# Electronic_Design_after_review_sch.net
KiCad netlist of a schematic drawn in EAGLE
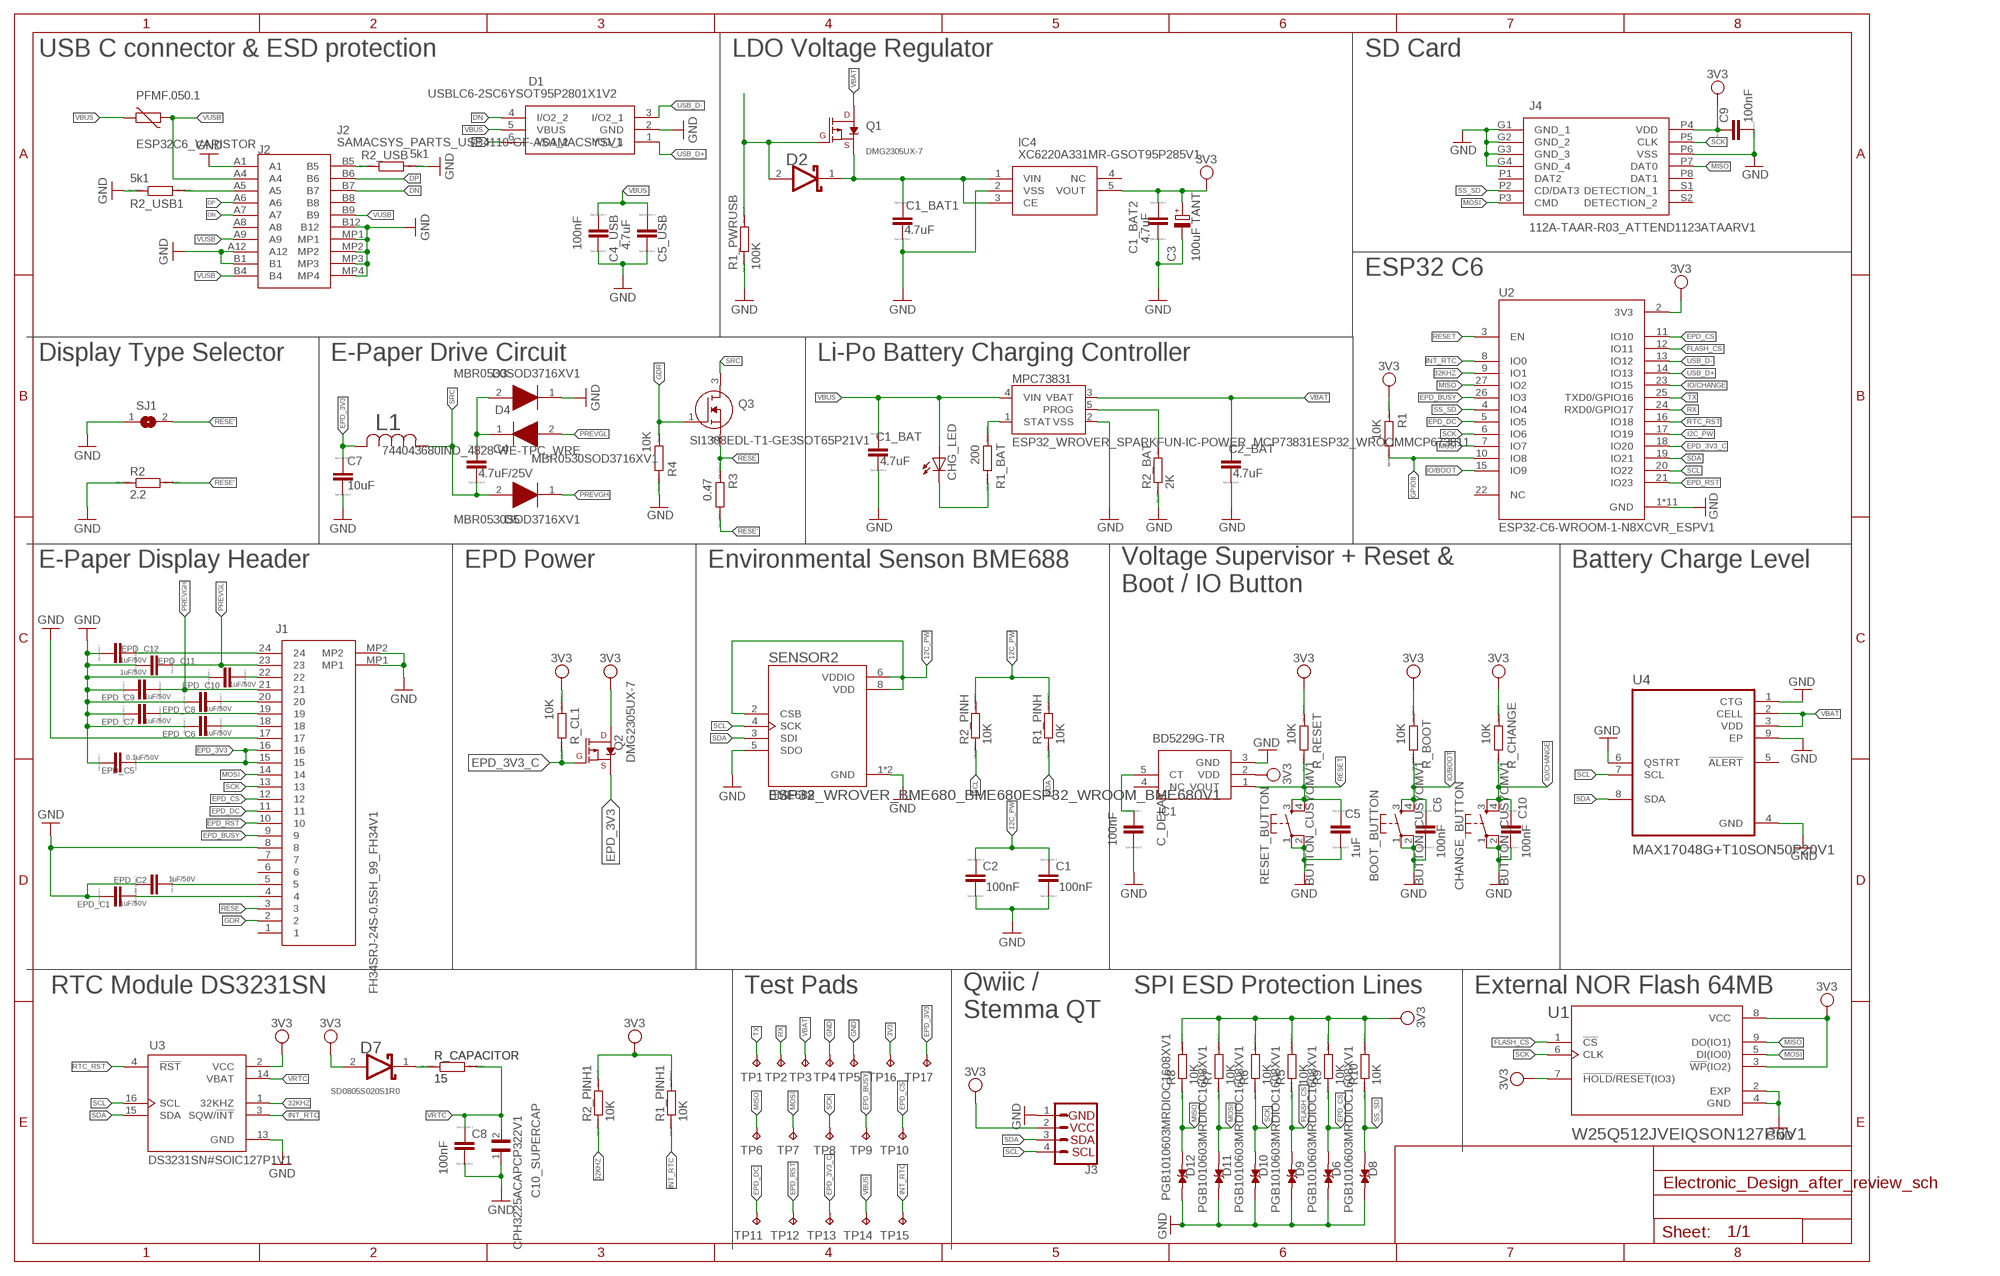
[diagram p0: schematic, sheet 1]

(export (version "E")
  (design (tool "Eeschema 10.0.6"))
  (components
    (comp (ref "BOOT_BUTTON")
      (value "BUTTON_CUSYOMV1")
      (footprint "eagle-import:MYBUTTON")
      (libsource (lib "eagle-import") (part "BUTTON_CUSYOMV1"))
    )
    (comp (ref "C1")
      (value "100nF")
      (footprint "eagle-import:EAGLE-LTSPICE_C0402")
      (libsource (lib "eagle-import") (part "EAGLE-LTSPICE_C"))
    )
    (comp (ref "C1_BAT")
      (value "4.7uF")
      (footprint "eagle-import:ESP32_WROVER_EAGLE-LTSPICE_C0402")
      (libsource (lib "eagle-import") (part "ESP32_WROVER_EAGLE-LTSPICE_C"))
    )
    (comp (ref "C1_BAT1")
      (value "4.7uF")
      (footprint "eagle-import:ESP32_WROVER_EAGLE-LTSPICE_C0402")
      (libsource (lib "eagle-import") (part "ESP32_WROVER_EAGLE-LTSPICE_C"))
    )
    (comp (ref "C1_BAT2")
      (value "4.7uF")
      (footprint "eagle-import:ESP32_WROVER_EAGLE-LTSPICE_C0402")
      (libsource (lib "eagle-import") (part "ESP32_WROVER_EAGLE-LTSPICE_C"))
    )
    (comp (ref "C2")
      (value "100nF")
      (footprint "eagle-import:EAGLE-LTSPICE_C0402")
      (libsource (lib "eagle-import") (part "EAGLE-LTSPICE_C"))
    )
    (comp (ref "C2_BAT")
      (value "4.7uF")
      (footprint "eagle-import:ESP32_WROVER_EAGLE-LTSPICE_C0402")
      (libsource (lib "eagle-import") (part "ESP32_WROVER_EAGLE-LTSPICE_C"))
    )
    (comp (ref "C3")
      (value "100uF TANT")
      (footprint "eagle-import:RCL_CT3528")
      (libsource (lib "eagle-import") (part "RCL_CPOL-EU"))
    )
    (comp (ref "C4")
      (value "4.7uF/25V")
      (footprint "eagle-import:ESP32_WROVER_EAGLE-LTSPICE_C0402")
      (libsource (lib "eagle-import") (part "ESP32_WROVER_EAGLE-LTSPICE_C"))
    )
    (comp (ref "C4_USB")
      (value "100nF")
      (footprint "eagle-import:ESP32_WROVER_EAGLE-LTSPICE_C0402")
      (libsource (lib "eagle-import") (part "ESP32_WROVER_EAGLE-LTSPICE_C"))
    )
    (comp (ref "C5")
      (value "1uF")
      (footprint "eagle-import:EAGLE-LTSPICE_C0402")
      (libsource (lib "eagle-import") (part "EAGLE-LTSPICE_C"))
    )
    (comp (ref "C5_USB")
      (value "4.7uF")
      (footprint "eagle-import:ESP32_WROVER_EAGLE-LTSPICE_C0402")
      (libsource (lib "eagle-import") (part "ESP32_WROVER_EAGLE-LTSPICE_C"))
    )
    (comp (ref "C6")
      (value "100nF")
      (footprint "eagle-import:EAGLE-LTSPICE_C0402")
      (libsource (lib "eagle-import") (part "EAGLE-LTSPICE_C"))
    )
    (comp (ref "C7")
      (value "10uF")
      (footprint "eagle-import:ESP32_WROVER_EAGLE-LTSPICE_C0402")
      (libsource (lib "eagle-import") (part "ESP32_WROVER_EAGLE-LTSPICE_C"))
    )
    (comp (ref "C8")
      (value "100nF")
      (footprint "eagle-import:EAGLE-LTSPICE_C0402")
      (libsource (lib "eagle-import") (part "EAGLE-LTSPICE_C"))
    )
    (comp (ref "C9")
      (value "100nF")
      (footprint "eagle-import:ESP32_WROVER_EAGLE-LTSPICE_C0402")
      (libsource (lib "eagle-import") (part "ESP32_WROVER_EAGLE-LTSPICE_C"))
    )
    (comp (ref "C10")
      (value "100nF")
      (footprint "eagle-import:EAGLE-LTSPICE_C0402")
      (libsource (lib "eagle-import") (part "EAGLE-LTSPICE_C"))
    )
    (comp (ref "C10_SUPERCAP")
      (value "CPH3225ACAPCP322V1")
      (footprint "eagle-import:CAPCP3225X100N")
      (libsource (lib "eagle-import") (part "CPH3225ACAPCP322V1"))
    )
    (comp (ref "CHANGE_BUTTON")
      (value "BUTTON_CUSYOMV1")
      (footprint "eagle-import:MYBUTTON")
      (libsource (lib "eagle-import") (part "BUTTON_CUSYOMV1"))
    )
    (comp (ref "CHG_LED")
      (value "ADAFRUIT_LED")
      (footprint "eagle-import:ADAFRUIT_CHIP-LED0603")
      (libsource (lib "eagle-import") (part "ADAFRUIT_LED"))
    )
    (comp (ref "C_DELAY")
      (value "100nF")
      (footprint "eagle-import:EAGLE-LTSPICE_C0402")
      (libsource (lib "eagle-import") (part "EAGLE-LTSPICE_C"))
    )
    (comp (ref "D1")
      (value "USBLC6-2SC6YSOT95P2801X1V2")
      (footprint "eagle-import:SOT95P280X145-6N")
      (libsource (lib "eagle-import") (part "USBLC6-2SC6YSOT95P2801X1V2"))
    )
    (comp (ref "D2")
      (value "ESP32_WROVER_AVX---SD0805S020S1R0_AVX_SD0805S020S1R0_0_0")
      (footprint "eagle-import:ESP32_WROVER_AVX---SD0805S020S1R0_AVX_SD0805S020S1R0_0")
      (libsource (lib "eagle-import") (part "ESP32_WROVER_AVX---SD0805S020S1R0_AVX_SD0805S020S1R0_0_0"))
    )
    (comp (ref "D3")
      (value "MBR0530SOD3716XV1")
      (footprint "eagle-import:SOD3716X135N")
      (libsource (lib "eagle-import") (part "MBR0530SOD3716XV1"))
    )
    (comp (ref "D4")
      (value "MBR0530SOD3716XV1")
      (footprint "eagle-import:SOD3716X135N")
      (libsource (lib "eagle-import") (part "MBR0530SOD3716XV1"))
    )
    (comp (ref "D5")
      (value "MBR0530SOD3716XV1")
      (footprint "eagle-import:SOD3716X135N")
      (libsource (lib "eagle-import") (part "MBR0530SOD3716XV1"))
    )
    (comp (ref "D6")
      (value "PGB1010603MRDIOC1608XV1")
      (footprint "eagle-import:DIOC1608X36N")
      (libsource (lib "eagle-import") (part "PGB1010603MRDIOC1608XV1"))
    )
    (comp (ref "D7")
      (value "ESP32_WROVER_AVX---SD0805S020S1R0_AVX_SD0805S020S1R0_0_0")
      (footprint "eagle-import:ESP32_WROVER_AVX---SD0805S020S1R0_AVX_SD0805S020S1R0_0")
      (libsource (lib "eagle-import") (part "ESP32_WROVER_AVX---SD0805S020S1R0_AVX_SD0805S020S1R0_0_0"))
    )
    (comp (ref "D8")
      (value "PGB1010603MRDIOC1608XV1")
      (footprint "eagle-import:DIOC1608X36N")
      (libsource (lib "eagle-import") (part "PGB1010603MRDIOC1608XV1"))
    )
    (comp (ref "D9")
      (value "PGB1010603MRDIOC1608XV1")
      (footprint "eagle-import:DIOC1608X36N")
      (libsource (lib "eagle-import") (part "PGB1010603MRDIOC1608XV1"))
    )
    (comp (ref "D10")
      (value "PGB1010603MRDIOC1608XV1")
      (footprint "eagle-import:DIOC1608X36N")
      (libsource (lib "eagle-import") (part "PGB1010603MRDIOC1608XV1"))
    )
    (comp (ref "D11")
      (value "PGB1010603MRDIOC1608XV1")
      (footprint "eagle-import:DIOC1608X36N")
      (libsource (lib "eagle-import") (part "PGB1010603MRDIOC1608XV1"))
    )
    (comp (ref "D12")
      (value "PGB1010603MRDIOC1608XV1")
      (footprint "eagle-import:DIOC1608X36N")
      (libsource (lib "eagle-import") (part "PGB1010603MRDIOC1608XV1"))
    )
    (comp (ref "EPD_C1")
      (value "1uF/50V")
      (footprint "eagle-import:EAGLE-LTSPICE_C0402")
      (libsource (lib "eagle-import") (part "EAGLE-LTSPICE_C"))
    )
    (comp (ref "EPD_C2")
      (value "1uF/50V")
      (footprint "eagle-import:EAGLE-LTSPICE_C0402")
      (libsource (lib "eagle-import") (part "EAGLE-LTSPICE_C"))
    )
    (comp (ref "EPD_C5")
      (value "0.1uF/50V")
      (footprint "eagle-import:EAGLE-LTSPICE_C0402")
      (libsource (lib "eagle-import") (part "EAGLE-LTSPICE_C"))
    )
    (comp (ref "EPD_C6")
      (value "1uF/50V")
      (footprint "eagle-import:EAGLE-LTSPICE_C0402")
      (libsource (lib "eagle-import") (part "EAGLE-LTSPICE_C"))
    )
    (comp (ref "EPD_C7")
      (value "1uF/50V")
      (footprint "eagle-import:EAGLE-LTSPICE_C0402")
      (libsource (lib "eagle-import") (part "EAGLE-LTSPICE_C"))
    )
    (comp (ref "EPD_C8")
      (value "1uF/50V")
      (footprint "eagle-import:EAGLE-LTSPICE_C0402")
      (libsource (lib "eagle-import") (part "EAGLE-LTSPICE_C"))
    )
    (comp (ref "EPD_C9")
      (value "1uF/50V")
      (footprint "eagle-import:EAGLE-LTSPICE_C0402")
      (libsource (lib "eagle-import") (part "EAGLE-LTSPICE_C"))
    )
    (comp (ref "EPD_C10")
      (value "1uF/50V")
      (footprint "eagle-import:EAGLE-LTSPICE_C0402")
      (libsource (lib "eagle-import") (part "EAGLE-LTSPICE_C"))
    )
    (comp (ref "EPD_C11")
      (value "1uF/50V")
      (footprint "eagle-import:EAGLE-LTSPICE_C0402")
      (libsource (lib "eagle-import") (part "EAGLE-LTSPICE_C"))
    )
    (comp (ref "EPD_C12")
      (value "1uF/50V")
      (footprint "eagle-import:EAGLE-LTSPICE_C0402")
      (libsource (lib "eagle-import") (part "EAGLE-LTSPICE_C"))
    )
    (comp (ref "IC1")
      (value "BD5229G-TR")
      (footprint "eagle-import:SOT95P280X120-5N")
      (libsource (lib "eagle-import") (part "BD5229G-TR"))
    )
    (comp (ref "IC4")
      (value "XC6220A331MR-GSOT95P285V1")
      (footprint "eagle-import:SOT95P280X120-5N")
      (libsource (lib "eagle-import") (part "XC6220A331MR-GSOT95P285V1"))
    )
    (comp (ref "J1")
      (value "FH34SRJ-24S-0.5SH_99_FH34V1")
      (footprint "eagle-import:FH34SRJ24S05SH99")
      (libsource (lib "eagle-import") (part "FH34SRJ-24S-0.5SH_99_FH34V1"))
    )
    (comp (ref "J2")
      (value "SAMACSYS_PARTS_USB4110-GF-ASAMACSYSV1")
      (footprint "eagle-import:SAMACSYS_PARTS_USB4110GFA")
      (libsource (lib "eagle-import") (part "SAMACSYS_PARTS_USB4110-GF-ASAMACSYSV1"))
    )
    (comp (ref "J3")
      (value "QWIIC_RIGHT_ANGLE")
      (footprint "eagle-import:JST04_1MM_RA")
      (libsource (lib "eagle-import") (part "QWIIC_CONNECTOR"))
    )
    (comp (ref "J4")
      (value "112A-TAAR-R03_ATTEND1123ATAARV1")
      (footprint "eagle-import:112ATAARR03ATTEND")
      (libsource (lib "eagle-import") (part "112A-TAAR-R03_ATTEND1123ATAARV1"))
    )
    (comp (ref "L1")
      (value "744043680IND_4828-WE-TPC_WRE")
      (footprint "eagle-import:IND_4828-WE-TPC_WRE")
      (libsource (lib "eagle-import") (part "744043680"))
    )
    (comp (ref "MPC73831")
      (value "ESP32_WROVER_SPARKFUN-IC-POWER_MCP73831ESP32_WROOMMCP673811")
      (footprint "eagle-import:ESP32_WROVER_SPARKFUN-IC-POWER_SOT23-5")
      (libsource (lib "eagle-import") (part "ESP32_WROVER_SPARKFUN-IC-POWER_MCP73831ESP32_WROOMMCP673811"))
    )
    (comp (ref "PFMF.050.1")
      (value "ESP32C6_VARISTOR")
      (footprint "eagle-import:ESP32C6_VARISTOR_CT_CN1812")
      (libsource (lib "eagle-import") (part "ESP32C6_VARISTOR"))
    )
    (comp (ref "Q1")
      (value "20V/4.2A/52mΩ/1.4W")
      (footprint "eagle-import:ESP32_WROVER_SPARKFUN-DISCRETESEMI_SOT23-3")
      (libsource (lib "eagle-import") (part "ESP32_WROVER_SPARKFUN-DISCRETESEMI_MOSFET_PCH"))
    )
    (comp (ref "Q2")
      (value "20V/4.2A/52mΩ/1.4W")
      (footprint "eagle-import:ESP32_WROVER_SPARKFUN-DISCRETESEMI_SOT23-3")
      (libsource (lib "eagle-import") (part "ESP32_WROVER_SPARKFUN-DISCRETESEMI_MOSFET_PCH"))
    )
    (comp (ref "Q3")
      (value "SI1308EDL-T1-GE3SOT65P21V1")
      (footprint "eagle-import:SOT65P210X110-3N")
      (libsource (lib "eagle-import") (part "SI1308EDL-T1-GE3SOT65P21V1"))
    )
    (comp (ref "R1")
      (value "10K")
      (footprint "eagle-import:ESP32_WROVER_EAGLE-LTSPICE_R0402")
      (libsource (lib "eagle-import") (part "ESP32_WROVER_EAGLE-LTSPICE_R"))
    )
    (comp (ref "R1_BAT")
      (value "200")
      (footprint "eagle-import:ESP32_WROVER_EAGLE-LTSPICE_R0402")
      (libsource (lib "eagle-import") (part "ESP32_WROVER_EAGLE-LTSPICE_R"))
    )
    (comp (ref "R1_PINH")
      (value "10K")
      (footprint "eagle-import:ESP32_WROVER_EAGLE-LTSPICE_R0402")
      (libsource (lib "eagle-import") (part "ESP32_WROVER_EAGLE-LTSPICE_R"))
    )
    (comp (ref "R1_PINH1")
      (value "10K")
      (footprint "eagle-import:ESP32_WROVER_EAGLE-LTSPICE_R0402")
      (libsource (lib "eagle-import") (part "ESP32_WROVER_EAGLE-LTSPICE_R"))
    )
    (comp (ref "R1_PWRUSB")
      (value "100K")
      (footprint "eagle-import:ESP32_WROVER_EAGLE-LTSPICE_R0402")
      (libsource (lib "eagle-import") (part "ESP32_WROVER_EAGLE-LTSPICE_R"))
    )
    (comp (ref "R2")
      (value "2.2")
      (footprint "eagle-import:ESP32_WROVER_EAGLE-LTSPICE_R0402")
      (libsource (lib "eagle-import") (part "ESP32_WROVER_EAGLE-LTSPICE_R"))
    )
    (comp (ref "R2_BAT")
      (value "2K")
      (footprint "eagle-import:ESP32_WROVER_EAGLE-LTSPICE_R0402")
      (libsource (lib "eagle-import") (part "ESP32_WROVER_EAGLE-LTSPICE_R"))
    )
    (comp (ref "R2_PINH")
      (value "10K")
      (footprint "eagle-import:ESP32_WROVER_EAGLE-LTSPICE_R0402")
      (libsource (lib "eagle-import") (part "ESP32_WROVER_EAGLE-LTSPICE_R"))
    )
    (comp (ref "R2_PINH1")
      (value "10K")
      (footprint "eagle-import:ESP32_WROVER_EAGLE-LTSPICE_R0402")
      (libsource (lib "eagle-import") (part "ESP32_WROVER_EAGLE-LTSPICE_R"))
    )
    (comp (ref "R2_USB")
      (value "5k1")
      (footprint "eagle-import:ESP32_WROVER_EAGLE-LTSPICE_R0402")
      (libsource (lib "eagle-import") (part "ESP32_WROVER_EAGLE-LTSPICE_R"))
    )
    (comp (ref "R2_USB1")
      (value "5k1")
      (footprint "eagle-import:ESP32_WROVER_EAGLE-LTSPICE_R0402")
      (libsource (lib "eagle-import") (part "ESP32_WROVER_EAGLE-LTSPICE_R"))
    )
    (comp (ref "R3")
      (value "0.47")
      (footprint "eagle-import:ESP32_WROVER_EAGLE-LTSPICE_R0402")
      (libsource (lib "eagle-import") (part "ESP32_WROVER_EAGLE-LTSPICE_R"))
    )
    (comp (ref "R4")
      (value "10K")
      (footprint "eagle-import:ESP32_WROVER_EAGLE-LTSPICE_R0402")
      (libsource (lib "eagle-import") (part "ESP32_WROVER_EAGLE-LTSPICE_R"))
    )
    (comp (ref "R5")
      (value "10K")
      (footprint "eagle-import:ESP32_WROVER_EAGLE-LTSPICE_R0402")
      (libsource (lib "eagle-import") (part "ESP32_WROVER_EAGLE-LTSPICE_R"))
    )
    (comp (ref "R6")
      (value "10K")
      (footprint "eagle-import:ESP32_WROVER_EAGLE-LTSPICE_R0402")
      (libsource (lib "eagle-import") (part "ESP32_WROVER_EAGLE-LTSPICE_R"))
    )
    (comp (ref "R7")
      (value "10K")
      (footprint "eagle-import:ESP32_WROVER_EAGLE-LTSPICE_R0402")
      (libsource (lib "eagle-import") (part "ESP32_WROVER_EAGLE-LTSPICE_R"))
    )
    (comp (ref "R8")
      (value "10K")
      (footprint "eagle-import:ESP32_WROVER_EAGLE-LTSPICE_R0402")
      (libsource (lib "eagle-import") (part "ESP32_WROVER_EAGLE-LTSPICE_R"))
    )
    (comp (ref "R9")
      (value "10K")
      (footprint "eagle-import:ESP32_WROVER_EAGLE-LTSPICE_R0402")
      (libsource (lib "eagle-import") (part "ESP32_WROVER_EAGLE-LTSPICE_R"))
    )
    (comp (ref "R10")
      (value "10K")
      (footprint "eagle-import:ESP32_WROVER_EAGLE-LTSPICE_R0402")
      (libsource (lib "eagle-import") (part "ESP32_WROVER_EAGLE-LTSPICE_R"))
    )
    (comp (ref "RESET_BUTTON")
      (value "BUTTON_CUSYOMV1")
      (footprint "eagle-import:MYBUTTON")
      (libsource (lib "eagle-import") (part "BUTTON_CUSYOMV1"))
    )
    (comp (ref "R_BOOT")
      (value "10K")
      (footprint "eagle-import:ESP32_WROVER_EAGLE-LTSPICE_R0402")
      (libsource (lib "eagle-import") (part "ESP32_WROVER_EAGLE-LTSPICE_R"))
    )
    (comp (ref "R_CAPACITOR")
      (value "15")
      (footprint "eagle-import:ESP32_WROVER_EAGLE-LTSPICE_R0402")
      (libsource (lib "eagle-import") (part "ESP32_WROVER_EAGLE-LTSPICE_R"))
    )
    (comp (ref "R_CHANGE")
      (value "10K")
      (footprint "eagle-import:ESP32_WROVER_EAGLE-LTSPICE_R0402")
      (libsource (lib "eagle-import") (part "ESP32_WROVER_EAGLE-LTSPICE_R"))
    )
    (comp (ref "R_CL1")
      (value "10K")
      (footprint "eagle-import:ESP32_WROVER_EAGLE-LTSPICE_R0402")
      (libsource (lib "eagle-import") (part "ESP32_WROVER_EAGLE-LTSPICE_R"))
    )
    (comp (ref "R_RESET")
      (value "10K")
      (footprint "eagle-import:ESP32_WROVER_EAGLE-LTSPICE_R0402")
      (libsource (lib "eagle-import") (part "ESP32_WROVER_EAGLE-LTSPICE_R"))
    )
    (comp (ref "SENSOR2")
      (value "ESP32_WROVER_BME680_BME680ESP32_WROOM_BME680V1")
      (footprint "eagle-import:ESP32_WROVER_BME680_PSON80P300X300X100-8N")
      (libsource (lib "eagle-import") (part "ESP32_WROVER_BME680_BME680ESP32_WROOM_BME680V1"))
    )
    (comp (ref "SJ1")
      (value "SJSJV1")
      (footprint "eagle-import:SJ")
      (libsource (lib "eagle-import") (part "SJSJV1"))
    )
    (comp (ref "TP1")
      (value "TP")
      (footprint "eagle-import:TP20R")
      (libsource (lib "eagle-import") (part "TP"))
    )
    (comp (ref "TP2")
      (value "TP")
      (footprint "eagle-import:TP20R")
      (libsource (lib "eagle-import") (part "TP"))
    )
    (comp (ref "TP3")
      (value "TP")
      (footprint "eagle-import:TP20R")
      (libsource (lib "eagle-import") (part "TP"))
    )
    (comp (ref "TP4")
      (value "TP")
      (footprint "eagle-import:TP20R")
      (libsource (lib "eagle-import") (part "TP"))
    )
    (comp (ref "TP5")
      (value "TP")
      (footprint "eagle-import:TP20R")
      (libsource (lib "eagle-import") (part "TP"))
    )
    (comp (ref "TP6")
      (value "TP")
      (footprint "eagle-import:TP20R")
      (libsource (lib "eagle-import") (part "TP"))
    )
    (comp (ref "TP7")
      (value "TP")
      (footprint "eagle-import:TP20R")
      (libsource (lib "eagle-import") (part "TP"))
    )
    (comp (ref "TP8")
      (value "TP")
      (footprint "eagle-import:TP20R")
      (libsource (lib "eagle-import") (part "TP"))
    )
    (comp (ref "TP9")
      (value "TP")
      (footprint "eagle-import:TP20R")
      (libsource (lib "eagle-import") (part "TP"))
    )
    (comp (ref "TP10")
      (value "TP")
      (footprint "eagle-import:TP20R")
      (libsource (lib "eagle-import") (part "TP"))
    )
    (comp (ref "TP11")
      (value "TP")
      (footprint "eagle-import:TP20R")
      (libsource (lib "eagle-import") (part "TP"))
    )
    (comp (ref "TP12")
      (value "TP")
      (footprint "eagle-import:TP20R")
      (libsource (lib "eagle-import") (part "TP"))
    )
    (comp (ref "TP13")
      (value "TP")
      (footprint "eagle-import:TP20R")
      (libsource (lib "eagle-import") (part "TP"))
    )
    (comp (ref "TP14")
      (value "TP")
      (footprint "eagle-import:TP20R")
      (libsource (lib "eagle-import") (part "TP"))
    )
    (comp (ref "TP15")
      (value "TP")
      (footprint "eagle-import:TP20R")
      (libsource (lib "eagle-import") (part "TP"))
    )
    (comp (ref "TP16")
      (value "TP")
      (footprint "eagle-import:TP20R")
      (libsource (lib "eagle-import") (part "TP"))
    )
    (comp (ref "TP17")
      (value "TP")
      (footprint "eagle-import:TP20R")
      (libsource (lib "eagle-import") (part "TP"))
    )
    (comp (ref "U1")
      (value "W25Q512JVEIQSON127P6V1")
      (footprint "eagle-import:SON127P600X800X80-9N")
      (libsource (lib "eagle-import") (part "W25Q512JVEIQSON127P6V1"))
    )
    (comp (ref "U2")
      (value "ESP32-C6-WROOM-1-N8XCVR_ESPV1")
      (footprint "eagle-import:XCVR_ESP32-C6-WROOM-1-N8")
      (libsource (lib "eagle-import") (part "ESP32-C6-WROOM-1-N8XCVR_ESPV1"))
    )
    (comp (ref "U3")
      (value "DS3231SN#SOIC127P1V1")
      (footprint "eagle-import:SOIC127P1032X265-16N")
      (libsource (lib "eagle-import") (part "DS3231SN#SOIC127P1V1"))
    )
    (comp (ref "U4")
      (value "MAX17048G+T10SON50P20V1")
      (footprint "eagle-import:SON50P200X200X80-9N")
      (libsource (lib "eagle-import") (part "MAX17048G+T10SON50P20V1"))
    )
  )
  (nets
    (net (code "1") (name "3V3") (class "Default")
      (node (ref "C1_BAT2") (pin "1") (pinfunction "1_1") (pintype "passive"))
      (node (ref "C3") (pin "+") (pinfunction "+_+") (pintype "passive"))
      (node (ref "C9") (pin "1") (pinfunction "1_1") (pintype "passive"))
      (node (ref "D7") (pin "2") (pinfunction "ANODE_2") (pintype "bidirectional"))
      (node (ref "IC1") (pin "2") (pinfunction "VDD_2") (pintype "bidirectional"))
      (node (ref "IC4") (pin "5") (pinfunction "VOUT_5") (pintype "bidirectional"))
      (node (ref "J3") (pin "2") (pinfunction "2_2") (pintype "power_in"))
      (node (ref "J4") (pin "P4") (pinfunction "VDD_P4") (pintype "bidirectional"))
      (node (ref "Q2") (pin "3") (pinfunction "D_3") (pintype "bidirectional"))
      (node (ref "R1") (pin "2") (pinfunction "2_2") (pintype "passive"))
      (node (ref "R10") (pin "2") (pinfunction "2_2") (pintype "passive"))
      (node (ref "R1_PINH1") (pin "2") (pinfunction "2_2") (pintype "passive"))
      (node (ref "R2_PINH1") (pin "2") (pinfunction "2_2") (pintype "passive"))
      (node (ref "R5") (pin "2") (pinfunction "2_2") (pintype "passive"))
      (node (ref "R6") (pin "2") (pinfunction "2_2") (pintype "passive"))
      (node (ref "R7") (pin "2") (pinfunction "2_2") (pintype "passive"))
      (node (ref "R8") (pin "2") (pinfunction "2_2") (pintype "passive"))
      (node (ref "R9") (pin "2") (pinfunction "2_2") (pintype "passive"))
      (node (ref "R_BOOT") (pin "2") (pinfunction "2_2") (pintype "passive"))
      (node (ref "R_CHANGE") (pin "2") (pinfunction "2_2") (pintype "passive"))
      (node (ref "R_CL1") (pin "2") (pinfunction "2_2") (pintype "passive"))
      (node (ref "R_RESET") (pin "2") (pinfunction "2_2") (pintype "passive"))
      (node (ref "TP16") (pin "TP") (pinfunction "TP_TP") (pintype "input"))
      (node (ref "U1") (pin "3") (pinfunction "~{WP}(IO2)_3") (pintype "bidirectional"))
      (node (ref "U1") (pin "7") (pinfunction "~{HOLD}/~{RESET}(IO3)_7") (pintype "bidirectional"))
      (node (ref "U1") (pin "8") (pinfunction "VCC_8") (pintype "power_in"))
      (node (ref "U2") (pin "2") (pinfunction "3V3_2") (pintype "power_in"))
      (node (ref "U3") (pin "2") (pinfunction "VCC_2") (pintype "power_in"))
    )
    (net (code "2") (name "12C_PW") (class "Default")
      (node (ref "C1") (pin "1") (pinfunction "1_1") (pintype "passive"))
      (node (ref "C2") (pin "1") (pinfunction "1_1") (pintype "passive"))
      (node (ref "R1_PINH") (pin "2") (pinfunction "2_2") (pintype "passive"))
      (node (ref "R2_PINH") (pin "2") (pinfunction "2_2") (pintype "passive"))
      (node (ref "SENSOR2") (pin "2") (pinfunction "CSB_2") (pintype "input"))
      (node (ref "SENSOR2") (pin "6") (pinfunction "VDDIO_6") (pintype "power_in"))
      (node (ref "SENSOR2") (pin "8") (pinfunction "VDD_8") (pintype "power_in"))
    )
    (net (code "3") (name "32KHZ") (class "Default")
      (node (ref "R2_PINH1") (pin "1") (pinfunction "1_1") (pintype "passive"))
      (node (ref "U2") (pin "9") (pinfunction "IO1_9") (pintype "bidirectional"))
      (node (ref "U3") (pin "1") (pinfunction "32KHZ_1") (pintype "output"))
    )
    (net (code "4") (name "DN") (class "Default")
      (node (ref "D1") (pin "4") (pinfunction "I/O2_2_4") (pintype "bidirectional"))
      (node (ref "J2") (pin "A7") (pinfunction "A7_A7") (pintype "bidirectional"))
      (node (ref "J2") (pin "B7") (pinfunction "B7_B7") (pintype "bidirectional"))
    )
    (net (code "5") (name "DP") (class "Default")
      (node (ref "D1") (pin "6") (pinfunction "I/O1_2_6") (pintype "bidirectional"))
      (node (ref "J2") (pin "A6") (pinfunction "A6_A6") (pintype "bidirectional"))
      (node (ref "J2") (pin "B6") (pinfunction "B6_B6") (pintype "bidirectional"))
    )
    (net (code "6") (name "EPD_3V3") (class "Default")
      (node (ref "C7") (pin "1") (pinfunction "1_1") (pintype "passive"))
      (node (ref "EPD_C5") (pin "2") (pinfunction "2_2") (pintype "passive"))
      (node (ref "J1") (pin "15") (pinfunction "15_15") (pintype "bidirectional"))
      (node (ref "J1") (pin "16") (pinfunction "16_16") (pintype "bidirectional"))
      (node (ref "L1") (pin "2") (pinfunction "2_2") (pintype "passive"))
      (node (ref "Q2") (pin "2") (pinfunction "S_2") (pintype "bidirectional"))
      (node (ref "TP17") (pin "TP") (pinfunction "TP_TP") (pintype "input"))
    )
    (net (code "7") (name "EPD_3V3_C") (class "Default")
      (node (ref "Q2") (pin "1") (pinfunction "G_1") (pintype "bidirectional"))
      (node (ref "R_CL1") (pin "1") (pinfunction "1_1") (pintype "passive"))
      (node (ref "TP13") (pin "TP") (pinfunction "TP_TP") (pintype "input"))
      (node (ref "U2") (pin "18") (pinfunction "IO20_18") (pintype "bidirectional"))
    )
    (net (code "8") (name "EPD_BUSY") (class "Default")
      (node (ref "J1") (pin "9") (pinfunction "9_9") (pintype "bidirectional"))
      (node (ref "TP9") (pin "TP") (pinfunction "TP_TP") (pintype "input"))
      (node (ref "U2") (pin "26") (pinfunction "IO3_26") (pintype "bidirectional"))
    )
    (net (code "9") (name "EPD_CS") (class "Default")
      (node (ref "D6") (pin "2") (pinfunction "2_2") (pintype "passive"))
      (node (ref "J1") (pin "12") (pinfunction "12_12") (pintype "bidirectional"))
      (node (ref "R9") (pin "1") (pinfunction "1_1") (pintype "passive"))
      (node (ref "TP10") (pin "TP") (pinfunction "TP_TP") (pintype "input"))
      (node (ref "U2") (pin "11") (pinfunction "IO10_11") (pintype "bidirectional"))
    )
    (net (code "10") (name "EPD_DC") (class "Default")
      (node (ref "J1") (pin "11") (pinfunction "11_11") (pintype "bidirectional"))
      (node (ref "TP11") (pin "TP") (pinfunction "TP_TP") (pintype "input"))
      (node (ref "U2") (pin "5") (pinfunction "IO5_5") (pintype "bidirectional"))
    )
    (net (code "11") (name "EPD_RST") (class "Default")
      (node (ref "J1") (pin "10") (pinfunction "10_10") (pintype "bidirectional"))
      (node (ref "TP12") (pin "TP") (pinfunction "TP_TP") (pintype "input"))
      (node (ref "U2") (pin "21") (pinfunction "IO23_21") (pintype "bidirectional"))
    )
    (net (code "12") (name "FLASH_CS") (class "Default")
      (node (ref "D9") (pin "2") (pinfunction "2_2") (pintype "passive"))
      (node (ref "R5") (pin "1") (pinfunction "1_1") (pintype "passive"))
      (node (ref "U1") (pin "1") (pinfunction "~{CS}_1") (pintype "input"))
      (node (ref "U2") (pin "12") (pinfunction "IO11_12") (pintype "bidirectional"))
    )
    (net (code "13") (name "GDR") (class "Default")
      (node (ref "J1") (pin "2") (pinfunction "2_2") (pintype "bidirectional"))
      (node (ref "Q3") (pin "1") (pinfunction "G_1") (pintype "bidirectional"))
      (node (ref "R4") (pin "2") (pinfunction "2_2") (pintype "passive"))
    )
    (net (code "14") (name "GND") (class "Default")
      (node (ref "BOOT_BUTTON") (pin "1") (pinfunction "1_1") (pintype "passive"))
      (node (ref "BOOT_BUTTON") (pin "2") (pinfunction "2_2") (pintype "passive"))
      (node (ref "C1") (pin "2") (pinfunction "2_2") (pintype "passive"))
      (node (ref "C10") (pin "2") (pinfunction "2_2") (pintype "passive"))
      (node (ref "C10_SUPERCAP") (pin "1") (pinfunction "1_1") (pintype "passive"))
      (node (ref "C1_BAT") (pin "2") (pinfunction "2_2") (pintype "passive"))
      (node (ref "C1_BAT1") (pin "2") (pinfunction "2_2") (pintype "passive"))
      (node (ref "C1_BAT2") (pin "2") (pinfunction "2_2") (pintype "passive"))
      (node (ref "C2") (pin "2") (pinfunction "2_2") (pintype "passive"))
      (node (ref "C2_BAT") (pin "2") (pinfunction "2_2") (pintype "passive"))
      (node (ref "C3") (pin "-") (pinfunction "-_-") (pintype "passive"))
      (node (ref "C4_USB") (pin "2") (pinfunction "2_2") (pintype "passive"))
      (node (ref "C5") (pin "2") (pinfunction "2_2") (pintype "passive"))
      (node (ref "C5_USB") (pin "2") (pinfunction "2_2") (pintype "passive"))
      (node (ref "C6") (pin "2") (pinfunction "2_2") (pintype "passive"))
      (node (ref "C7") (pin "2") (pinfunction "2_2") (pintype "passive"))
      (node (ref "C8") (pin "2") (pinfunction "2_2") (pintype "passive"))
      (node (ref "C9") (pin "2") (pinfunction "2_2") (pintype "passive"))
      (node (ref "CHANGE_BUTTON") (pin "1") (pinfunction "1_1") (pintype "passive"))
      (node (ref "CHANGE_BUTTON") (pin "2") (pinfunction "2_2") (pintype "passive"))
      (node (ref "C_DELAY") (pin "2") (pinfunction "2_2") (pintype "passive"))
      (node (ref "D1") (pin "2") (pinfunction "GND_2") (pintype "bidirectional"))
      (node (ref "D10") (pin "1") (pinfunction "1_1") (pintype "passive"))
      (node (ref "D11") (pin "1") (pinfunction "1_1") (pintype "passive"))
      (node (ref "D12") (pin "1") (pinfunction "1_1") (pintype "passive"))
      (node (ref "D3") (pin "1") (pinfunction "K_1") (pintype "bidirectional"))
      (node (ref "D6") (pin "1") (pinfunction "1_1") (pintype "passive"))
      (node (ref "D8") (pin "1") (pinfunction "1_1") (pintype "passive"))
      (node (ref "D9") (pin "1") (pinfunction "1_1") (pintype "passive"))
      (node (ref "EPD_C1") (pin "1") (pinfunction "1_1") (pintype "passive"))
      (node (ref "EPD_C10") (pin "1") (pinfunction "1_1") (pintype "passive"))
      (node (ref "EPD_C11") (pin "1") (pinfunction "1_1") (pintype "passive"))
      (node (ref "EPD_C12") (pin "1") (pinfunction "1_1") (pintype "passive"))
      (node (ref "EPD_C2") (pin "1") (pinfunction "1_1") (pintype "passive"))
      (node (ref "EPD_C5") (pin "1") (pinfunction "1_1") (pintype "passive"))
      (node (ref "EPD_C6") (pin "1") (pinfunction "1_1") (pintype "passive"))
      (node (ref "EPD_C7") (pin "1") (pinfunction "1_1") (pintype "passive"))
      (node (ref "EPD_C8") (pin "1") (pinfunction "1_1") (pintype "passive"))
      (node (ref "EPD_C9") (pin "1") (pinfunction "1_1") (pintype "passive"))
      (node (ref "IC1") (pin "3") (pinfunction "GND_3") (pintype "bidirectional"))
      (node (ref "IC4") (pin "2") (pinfunction "VSS_2") (pintype "bidirectional"))
      (node (ref "J1") (pin "17") (pinfunction "17_17") (pintype "bidirectional"))
      (node (ref "J1") (pin "8") (pinfunction "8_8") (pintype "bidirectional"))
      (node (ref "J1") (pin "MP1") (pinfunction "MP1_MP1") (pintype "bidirectional"))
      (node (ref "J1") (pin "MP2") (pinfunction "MP2_MP2") (pintype "bidirectional"))
      (node (ref "J2") (pin "A1") (pinfunction "A1_A1") (pintype "bidirectional"))
      (node (ref "J2") (pin "A12") (pinfunction "A12_A12") (pintype "bidirectional"))
      (node (ref "J2") (pin "B1") (pinfunction "B1_B1") (pintype "bidirectional"))
      (node (ref "J2") (pin "B12") (pinfunction "B12_B12") (pintype "bidirectional"))
      (node (ref "J2") (pin "MP1") (pinfunction "MP1_MP1") (pintype "bidirectional"))
      (node (ref "J2") (pin "MP2") (pinfunction "MP2_MP2") (pintype "bidirectional"))
      (node (ref "J2") (pin "MP3") (pinfunction "MP3_MP3") (pintype "bidirectional"))
      (node (ref "J2") (pin "MP4") (pinfunction "MP4_MP4") (pintype "bidirectional"))
      (node (ref "J3") (pin "1") (pinfunction "1_1") (pintype "power_in"))
      (node (ref "J4") (pin "G1") (pinfunction "GND_1_G1") (pintype "bidirectional"))
      (node (ref "J4") (pin "G2") (pinfunction "GND_2_G2") (pintype "bidirectional"))
      (node (ref "J4") (pin "G3") (pinfunction "GND_3_G3") (pintype "bidirectional"))
      (node (ref "J4") (pin "G4") (pinfunction "GND_4_G4") (pintype "bidirectional"))
      (node (ref "J4") (pin "P6") (pinfunction "VSS_P6") (pintype "bidirectional"))
      (node (ref "MPC73831") (pin "2") (pinfunction "VSS_2") (pintype "power_in"))
      (node (ref "R1_PWRUSB") (pin "1") (pinfunction "1_1") (pintype "passive"))
      (node (ref "R2") (pin "1") (pinfunction "1_1") (pintype "passive"))
      (node (ref "R2_BAT") (pin "1") (pinfunction "1_1") (pintype "passive"))
      (node (ref "R2_USB") (pin "2") (pinfunction "2_2") (pintype "passive"))
      (node (ref "R2_USB1") (pin "1") (pinfunction "1_1") (pintype "passive"))
      (node (ref "R4") (pin "1") (pinfunction "1_1") (pintype "passive"))
      (node (ref "RESET_BUTTON") (pin "1") (pinfunction "1_1") (pintype "passive"))
      (node (ref "RESET_BUTTON") (pin "2") (pinfunction "2_2") (pintype "passive"))
      (node (ref "SENSOR2") (pin "1") (pinfunction "GND_1") (pintype "power_in"))
      (node (ref "SENSOR2") (pin "5") (pinfunction "SDO_5") (pintype "bidirectional"))
      (node (ref "SENSOR2") (pin "7") (pinfunction "GND_7") (pintype "power_in"))
      (node (ref "SJ1") (pin "1") (pinfunction "1_1") (pintype "passive"))
      (node (ref "TP4") (pin "TP") (pinfunction "TP_TP") (pintype "input"))
      (node (ref "TP5") (pin "TP") (pinfunction "TP_TP") (pintype "input"))
      (node (ref "U1") (pin "2") (pinfunction "EXP_2") (pintype "passive"))
      (node (ref "U1") (pin "4") (pinfunction "GND_4") (pintype "power_in"))
      (node (ref "U2") (pin "1") (pinfunction "GND_1") (pintype "power_in"))
      (node (ref "U2") (pin "28") (pinfunction "GND_28") (pintype "power_in"))
      (node (ref "U2") (pin "29_1") (pinfunction "GND_29_1") (pintype "power_in"))
      (node (ref "U2") (pin "29_2") (pinfunction "GND_29_2") (pintype "power_in"))
      (node (ref "U2") (pin "29_3") (pinfunction "GND_29_3") (pintype "power_in"))
      (node (ref "U2") (pin "29_4") (pinfunction "GND_29_4") (pintype "power_in"))
      (node (ref "U2") (pin "29_5") (pinfunction "GND_29_5") (pintype "power_in"))
      (node (ref "U2") (pin "29_6") (pinfunction "GND_29_6") (pintype "power_in"))
      (node (ref "U2") (pin "29_7") (pinfunction "GND_29_7") (pintype "power_in"))
      (node (ref "U2") (pin "29_8") (pinfunction "GND_29_8") (pintype "power_in"))
      (node (ref "U2") (pin "29_9") (pinfunction "GND_29_9") (pintype "power_in"))
      (node (ref "U3") (pin "13") (pinfunction "GND_13") (pintype "power_in"))
      (node (ref "U4") (pin "1") (pinfunction "CTG_1") (pintype "power_in"))
      (node (ref "U4") (pin "4") (pinfunction "GND_4") (pintype "power_in"))
      (node (ref "U4") (pin "6") (pinfunction "QSTRT_6") (pintype "input"))
      (node (ref "U4") (pin "9") (pinfunction "EP_9") (pintype "power_in"))
    )
    (net (code "15") (name "GPIO8") (class "Default")
      (node (ref "R1") (pin "1") (pinfunction "1_1") (pintype "passive"))
      (node (ref "U2") (pin "10") (pinfunction "IO8_10") (pintype "bidirectional"))
    )
    (net (code "16") (name "I2C_PW") (class "Default")
      (node (ref "U2") (pin "17") (pinfunction "IO19_17") (pintype "bidirectional"))
    )
    (net (code "17") (name "INT_RTC") (class "Default")
      (node (ref "R1_PINH1") (pin "1") (pinfunction "1_1") (pintype "passive"))
      (node (ref "TP15") (pin "TP") (pinfunction "TP_TP") (pintype "input"))
      (node (ref "U2") (pin "8") (pinfunction "IO0_8") (pintype "bidirectional"))
      (node (ref "U3") (pin "3") (pinfunction "SQW/~{INT}_3") (pintype "output"))
    )
    (net (code "18") (name "IO{slash}BOOT") (class "Default")
      (node (ref "BOOT_BUTTON") (pin "3") (pinfunction "3_3") (pintype "passive"))
      (node (ref "BOOT_BUTTON") (pin "4") (pinfunction "4_4") (pintype "passive"))
      (node (ref "C6") (pin "1") (pinfunction "1_1") (pintype "passive"))
      (node (ref "R_BOOT") (pin "1") (pinfunction "1_1") (pintype "passive"))
      (node (ref "U2") (pin "15") (pinfunction "IO9_15") (pintype "bidirectional"))
    )
    (net (code "19") (name "IO{slash}CHANGE") (class "Default")
      (node (ref "C10") (pin "1") (pinfunction "1_1") (pintype "passive"))
      (node (ref "CHANGE_BUTTON") (pin "3") (pinfunction "3_3") (pintype "passive"))
      (node (ref "CHANGE_BUTTON") (pin "4") (pinfunction "4_4") (pintype "passive"))
      (node (ref "R_CHANGE") (pin "1") (pinfunction "1_1") (pintype "passive"))
      (node (ref "U2") (pin "23") (pinfunction "IO15_23") (pintype "bidirectional"))
    )
    (net (code "20") (name "MISO") (class "Default")
      (node (ref "D12") (pin "2") (pinfunction "2_2") (pintype "passive"))
      (node (ref "J4") (pin "P7") (pinfunction "DAT0_P7") (pintype "bidirectional"))
      (node (ref "R8") (pin "1") (pinfunction "1_1") (pintype "passive"))
      (node (ref "TP6") (pin "TP") (pinfunction "TP_TP") (pintype "input"))
      (node (ref "U1") (pin "9") (pinfunction "DO(IO1)_9") (pintype "bidirectional"))
      (node (ref "U2") (pin "27") (pinfunction "IO2_27") (pintype "bidirectional"))
    )
    (net (code "21") (name "MOSI") (class "Default")
      (node (ref "D11") (pin "2") (pinfunction "2_2") (pintype "passive"))
      (node (ref "J1") (pin "14") (pinfunction "14_14") (pintype "bidirectional"))
      (node (ref "J4") (pin "P3") (pinfunction "CMD_P3") (pintype "bidirectional"))
      (node (ref "R7") (pin "1") (pinfunction "1_1") (pintype "passive"))
      (node (ref "TP7") (pin "TP") (pinfunction "TP_TP") (pintype "input"))
      (node (ref "U1") (pin "5") (pinfunction "DI(IO0)_5") (pintype "bidirectional"))
      (node (ref "U2") (pin "7") (pinfunction "IO7_7") (pintype "bidirectional"))
    )
    (net (code "22") (name "Net-(CHG_LED-PadC)") (class "Default")
      (node (ref "CHG_LED") (pin "C") (pinfunction "C_C") (pintype "passive"))
      (node (ref "R1_BAT") (pin "1") (pinfunction "1_1") (pintype "passive"))
    )
    (net (code "23") (name "Net-(D2-ANODE)") (class "Default")
      (node (ref "D2") (pin "2") (pinfunction "ANODE_2") (pintype "bidirectional"))
      (node (ref "Q1") (pin "1") (pinfunction "G_1") (pintype "bidirectional"))
      (node (ref "R1_PWRUSB") (pin "2") (pinfunction "2_2") (pintype "passive"))
    )
    (net (code "24") (name "Net-(D2-CATHODE)") (class "Default")
      (node (ref "C1_BAT1") (pin "1") (pinfunction "1_1") (pintype "passive"))
      (node (ref "D2") (pin "1") (pinfunction "CATHODE_1") (pintype "bidirectional"))
      (node (ref "IC4") (pin "1") (pinfunction "VIN_1") (pintype "bidirectional"))
      (node (ref "IC4") (pin "3") (pinfunction "CE_3") (pintype "bidirectional"))
      (node (ref "Q1") (pin "2") (pinfunction "S_2") (pintype "bidirectional"))
    )
    (net (code "25") (name "Net-(D3-A)") (class "Default")
      (node (ref "C4") (pin "1") (pinfunction "1_1") (pintype "passive"))
      (node (ref "D3") (pin "2") (pinfunction "A_2") (pintype "bidirectional"))
      (node (ref "D4") (pin "1") (pinfunction "K_1") (pintype "bidirectional"))
    )
    (net (code "26") (name "Net-(D7-CATHODE)") (class "Default")
      (node (ref "D7") (pin "1") (pinfunction "CATHODE_1") (pintype "bidirectional"))
      (node (ref "R_CAPACITOR") (pin "1") (pinfunction "1_1") (pintype "passive"))
    )
    (net (code "27") (name "Net-(EPD_C1-Pad2)") (class "Default")
      (node (ref "EPD_C1") (pin "2") (pinfunction "2_2") (pintype "passive"))
      (node (ref "J1") (pin "4") (pinfunction "4_4") (pintype "bidirectional"))
    )
    (net (code "28") (name "Net-(EPD_C2-Pad2)") (class "Default")
      (node (ref "EPD_C2") (pin "2") (pinfunction "2_2") (pintype "passive"))
      (node (ref "J1") (pin "5") (pinfunction "5_5") (pintype "bidirectional"))
    )
    (net (code "29") (name "Net-(EPD_C6-Pad2)") (class "Default")
      (node (ref "EPD_C6") (pin "2") (pinfunction "2_2") (pintype "passive"))
      (node (ref "J1") (pin "18") (pinfunction "18_18") (pintype "bidirectional"))
    )
    (net (code "30") (name "Net-(EPD_C7-Pad2)") (class "Default")
      (node (ref "EPD_C7") (pin "2") (pinfunction "2_2") (pintype "passive"))
      (node (ref "J1") (pin "19") (pinfunction "19_19") (pintype "bidirectional"))
    )
    (net (code "31") (name "Net-(EPD_C8-Pad2)") (class "Default")
      (node (ref "EPD_C8") (pin "2") (pinfunction "2_2") (pintype "passive"))
      (node (ref "J1") (pin "20") (pinfunction "20_20") (pintype "bidirectional"))
    )
    (net (code "32") (name "Net-(EPD_C10-Pad2)") (class "Default")
      (node (ref "EPD_C10") (pin "2") (pinfunction "2_2") (pintype "passive"))
      (node (ref "J1") (pin "22") (pinfunction "22_22") (pintype "bidirectional"))
    )
    (net (code "33") (name "Net-(EPD_C12-Pad2)") (class "Default")
      (node (ref "EPD_C12") (pin "2") (pinfunction "2_2") (pintype "passive"))
      (node (ref "J1") (pin "24") (pinfunction "24_24") (pintype "bidirectional"))
    )
    (net (code "34") (name "Net-(IC1-CT)") (class "Default")
      (node (ref "C_DELAY") (pin "1") (pinfunction "1_1") (pintype "passive"))
      (node (ref "IC1") (pin "5") (pinfunction "CT_5") (pintype "bidirectional"))
    )
    (net (code "35") (name "Net-(J2-PadA5)") (class "Default")
      (node (ref "J2") (pin "A5") (pinfunction "A5_A5") (pintype "bidirectional"))
      (node (ref "R2_USB1") (pin "2") (pinfunction "2_2") (pintype "passive"))
    )
    (net (code "36") (name "Net-(J2-PadB5)") (class "Default")
      (node (ref "J2") (pin "B5") (pinfunction "B5_B5") (pintype "bidirectional"))
      (node (ref "R2_USB") (pin "1") (pinfunction "1_1") (pintype "passive"))
    )
    (net (code "37") (name "Net-(MPC73831-PROG)") (class "Default")
      (node (ref "MPC73831") (pin "5") (pinfunction "PROG_5") (pintype "input"))
      (node (ref "R2_BAT") (pin "2") (pinfunction "2_2") (pintype "passive"))
    )
    (net (code "38") (name "Net-(MPC73831-STAT)") (class "Default")
      (node (ref "MPC73831") (pin "1") (pinfunction "STAT_1") (pintype "output"))
      (node (ref "R1_BAT") (pin "2") (pinfunction "2_2") (pintype "passive"))
    )
    (net (code "39") (name "PREVGH") (class "Default")
      (node (ref "D5") (pin "1") (pinfunction "K_1") (pintype "bidirectional"))
      (node (ref "EPD_C9") (pin "2") (pinfunction "2_2") (pintype "passive"))
      (node (ref "J1") (pin "21") (pinfunction "21_21") (pintype "bidirectional"))
    )
    (net (code "40") (name "PREVGL") (class "Default")
      (node (ref "D4") (pin "2") (pinfunction "A_2") (pintype "bidirectional"))
      (node (ref "EPD_C11") (pin "2") (pinfunction "2_2") (pintype "passive"))
      (node (ref "J1") (pin "23") (pinfunction "23_23") (pintype "bidirectional"))
    )
    (net (code "41") (name "RESE") (class "Default")
      (node (ref "J1") (pin "3") (pinfunction "3_3") (pintype "bidirectional"))
      (node (ref "Q3") (pin "2") (pinfunction "S_2") (pintype "bidirectional"))
      (node (ref "R3") (pin "2") (pinfunction "2_2") (pintype "passive"))
    )
    (net (code "42") (name "RESE'") (class "Default")
      (node (ref "R2") (pin "2") (pinfunction "2_2") (pintype "passive"))
      (node (ref "R3") (pin "1") (pinfunction "1_1") (pintype "passive"))
      (node (ref "SJ1") (pin "2") (pinfunction "2_2") (pintype "passive"))
    )
    (net (code "43") (name "RESET") (class "Default")
      (node (ref "C5") (pin "1") (pinfunction "1_1") (pintype "passive"))
      (node (ref "IC1") (pin "1") (pinfunction "VOUT_1") (pintype "bidirectional"))
      (node (ref "RESET_BUTTON") (pin "3") (pinfunction "3_3") (pintype "passive"))
      (node (ref "RESET_BUTTON") (pin "4") (pinfunction "4_4") (pintype "passive"))
      (node (ref "R_RESET") (pin "1") (pinfunction "1_1") (pintype "passive"))
      (node (ref "U2") (pin "3") (pinfunction "EN_3") (pintype "input"))
    )
    (net (code "44") (name "RTC_RST") (class "Default")
      (node (ref "U2") (pin "16") (pinfunction "IO18_16") (pintype "bidirectional"))
      (node (ref "U3") (pin "4") (pinfunction "~{RST}_4") (pintype "input"))
    )
    (net (code "45") (name "RX") (class "Default")
      (node (ref "TP2") (pin "TP") (pinfunction "TP_TP") (pintype "input"))
      (node (ref "U2") (pin "24") (pinfunction "RXD0/GPIO17_24") (pintype "bidirectional"))
    )
    (net (code "46") (name "SCK") (class "Default")
      (node (ref "D10") (pin "2") (pinfunction "2_2") (pintype "passive"))
      (node (ref "J1") (pin "13") (pinfunction "13_13") (pintype "bidirectional"))
      (node (ref "J4") (pin "P5") (pinfunction "CLK_P5") (pintype "bidirectional"))
      (node (ref "R6") (pin "1") (pinfunction "1_1") (pintype "passive"))
      (node (ref "TP8") (pin "TP") (pinfunction "TP_TP") (pintype "input"))
      (node (ref "U1") (pin "6") (pinfunction "CLK_6") (pintype "input"))
      (node (ref "U2") (pin "6") (pinfunction "IO6_6") (pintype "bidirectional"))
    )
    (net (code "47") (name "SCL") (class "Default")
      (node (ref "J3") (pin "4") (pinfunction "4_4") (pintype "passive"))
      (node (ref "R2_PINH") (pin "1") (pinfunction "1_1") (pintype "passive"))
      (node (ref "SENSOR2") (pin "4") (pinfunction "SCK_4") (pintype "input"))
      (node (ref "U2") (pin "20") (pinfunction "IO22_20") (pintype "bidirectional"))
      (node (ref "U3") (pin "16") (pinfunction "SCL_16") (pintype "input"))
      (node (ref "U4") (pin "7") (pinfunction "SCL_7") (pintype "input"))
    )
    (net (code "48") (name "SDA") (class "Default")
      (node (ref "J3") (pin "3") (pinfunction "3_3") (pintype "passive"))
      (node (ref "R1_PINH") (pin "1") (pinfunction "1_1") (pintype "passive"))
      (node (ref "SENSOR2") (pin "3") (pinfunction "SDI_3") (pintype "bidirectional"))
      (node (ref "U2") (pin "19") (pinfunction "IO21_19") (pintype "bidirectional"))
      (node (ref "U3") (pin "15") (pinfunction "SDA_15") (pintype "bidirectional"))
      (node (ref "U4") (pin "8") (pinfunction "SDA_8") (pintype "bidirectional"))
    )
    (net (code "49") (name "SRC") (class "Default")
      (node (ref "C4") (pin "2") (pinfunction "2_2") (pintype "passive"))
      (node (ref "D5") (pin "2") (pinfunction "A_2") (pintype "bidirectional"))
      (node (ref "L1") (pin "1") (pinfunction "1_1") (pintype "passive"))
      (node (ref "Q3") (pin "3") (pinfunction "D_3") (pintype "bidirectional"))
    )
    (net (code "50") (name "SS_SD") (class "Default")
      (node (ref "D8") (pin "2") (pinfunction "2_2") (pintype "passive"))
      (node (ref "J4") (pin "P2") (pinfunction "CD/DAT3_P2") (pintype "bidirectional"))
      (node (ref "R10") (pin "1") (pinfunction "1_1") (pintype "passive"))
      (node (ref "U2") (pin "4") (pinfunction "IO4_4") (pintype "bidirectional"))
    )
    (net (code "51") (name "TX") (class "Default")
      (node (ref "TP1") (pin "TP") (pinfunction "TP_TP") (pintype "input"))
      (node (ref "U2") (pin "25") (pinfunction "TXD0/GPIO16_25") (pintype "bidirectional"))
    )
    (net (code "52") (name "USB_D+") (class "Default")
      (node (ref "D1") (pin "1") (pinfunction "I/O1_1_1") (pintype "bidirectional"))
      (node (ref "U2") (pin "14") (pinfunction "IO13_14") (pintype "bidirectional"))
    )
    (net (code "53") (name "USB_D-") (class "Default")
      (node (ref "D1") (pin "3") (pinfunction "I/O2_1_3") (pintype "bidirectional"))
      (node (ref "U2") (pin "13") (pinfunction "IO12_13") (pintype "bidirectional"))
    )
    (net (code "54") (name "VBAT") (class "Default")
      (node (ref "C2_BAT") (pin "1") (pinfunction "1_1") (pintype "passive"))
      (node (ref "MPC73831") (pin "3") (pinfunction "VBAT_3") (pintype "power_in"))
      (node (ref "Q1") (pin "3") (pinfunction "D_3") (pintype "bidirectional"))
      (node (ref "TP3") (pin "TP") (pinfunction "TP_TP") (pintype "input"))
      (node (ref "U4") (pin "2") (pinfunction "CELL_2") (pintype "power_in"))
      (node (ref "U4") (pin "3") (pinfunction "VDD_3") (pintype "power_in"))
    )
    (net (code "55") (name "VBUS") (class "Default")
      (node (ref "C1_BAT") (pin "1") (pinfunction "1_1") (pintype "passive"))
      (node (ref "C4_USB") (pin "1") (pinfunction "1_1") (pintype "passive"))
      (node (ref "C5_USB") (pin "1") (pinfunction "1_1") (pintype "passive"))
      (node (ref "CHG_LED") (pin "A") (pinfunction "A_A") (pintype "passive"))
      (node (ref "D1") (pin "5") (pinfunction "VBUS_5") (pintype "bidirectional"))
      (node (ref "MPC73831") (pin "4") (pinfunction "VIN_4") (pintype "power_in"))
      (node (ref "PFMF.050.1") (pin "2") (pinfunction "2_2") (pintype "passive"))
      (node (ref "TP14") (pin "TP") (pinfunction "TP_TP") (pintype "input"))
    )
    (net (code "56") (name "VRTC") (class "Default")
      (node (ref "C10_SUPERCAP") (pin "2") (pinfunction "2_2") (pintype "passive"))
      (node (ref "C8") (pin "1") (pinfunction "1_1") (pintype "passive"))
      (node (ref "R_CAPACITOR") (pin "2") (pinfunction "2_2") (pintype "passive"))
      (node (ref "U3") (pin "14") (pinfunction "VBAT_14") (pintype "power_in"))
    )
    (net (code "57") (name "VUSB") (class "Default")
      (node (ref "J2") (pin "A4") (pinfunction "A4_A4") (pintype "bidirectional"))
      (node (ref "J2") (pin "A9") (pinfunction "A9_A9") (pintype "bidirectional"))
      (node (ref "J2") (pin "B4") (pinfunction "B4_B4") (pintype "bidirectional"))
      (node (ref "J2") (pin "B9") (pinfunction "B9_B9") (pintype "bidirectional"))
      (node (ref "PFMF.050.1") (pin "1") (pinfunction "1_1") (pintype "passive"))
    )
    (net (code "58") (name "unconnected-(IC1-NC-Pad4)") (class "Default")
      (node (ref "IC1") (pin "4") (pinfunction "NC_4") (pintype "no_connect"))
    )
    (net (code "59") (name "unconnected-(IC4-NC-Pad4)") (class "Default")
      (node (ref "IC4") (pin "4") (pinfunction "NC_4") (pintype "no_connect"))
    )
    (net (code "60") (name "unconnected-(J1-Pad1)") (class "Default")
      (node (ref "J1") (pin "1") (pinfunction "1_1") (pintype "bidirectional"))
    )
    (net (code "61") (name "unconnected-(J1-Pad6)") (class "Default")
      (node (ref "J1") (pin "6") (pinfunction "6_6") (pintype "bidirectional"))
    )
    (net (code "62") (name "unconnected-(J1-Pad7)") (class "Default")
      (node (ref "J1") (pin "7") (pinfunction "7_7") (pintype "bidirectional"))
    )
    (net (code "63") (name "unconnected-(J2-PadA8)") (class "Default")
      (node (ref "J2") (pin "A8") (pinfunction "A8_A8") (pintype "bidirectional"))
    )
    (net (code "64") (name "unconnected-(J2-PadB8)") (class "Default")
      (node (ref "J2") (pin "B8") (pinfunction "B8_B8") (pintype "bidirectional"))
    )
    (net (code "65") (name "unconnected-(J4-DAT1-PadP8)") (class "Default")
      (node (ref "J4") (pin "P8") (pinfunction "DAT1_P8") (pintype "bidirectional"))
    )
    (net (code "66") (name "unconnected-(J4-DAT2-PadP1)") (class "Default")
      (node (ref "J4") (pin "P1") (pinfunction "DAT2_P1") (pintype "bidirectional"))
    )
    (net (code "67") (name "unconnected-(J4-DETECTION_1-PadS1)") (class "Default")
      (node (ref "J4") (pin "S1") (pinfunction "DETECTION_1_S1") (pintype "bidirectional"))
    )
    (net (code "68") (name "unconnected-(J4-DETECTION_2-PadS2)") (class "Default")
      (node (ref "J4") (pin "S2") (pinfunction "DETECTION_2_S2") (pintype "bidirectional"))
    )
    (net (code "69") (name "unconnected-(U2-NC-Pad22)") (class "Default")
      (node (ref "U2") (pin "22") (pinfunction "NC_22") (pintype "no_connect"))
    )
    (net (code "70") (name "unconnected-(U4-~{ALERT}-Pad5)") (class "Default")
      (node (ref "U4") (pin "5") (pinfunction "~{ALERT}_5") (pintype "output"))
    )
  )
)
